# LiquidCrystal595.net
KiCad netlist of a schematic drawn in EAGLE
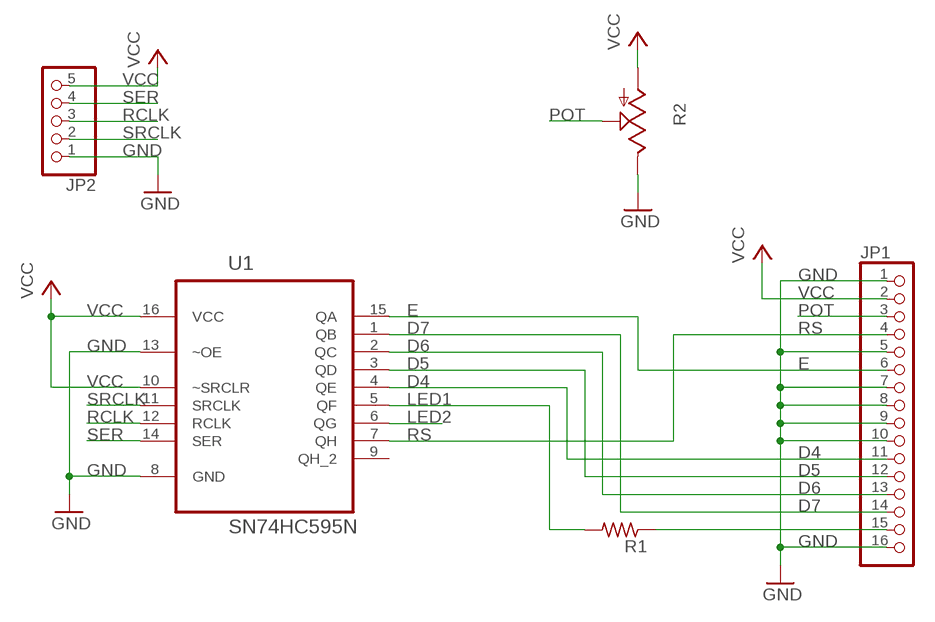
[diagram p0: schematic, sheet 1]

(export (version "E")
  (design (tool "Eeschema 10.0.6"))
  (components
    (comp (ref "JP1")
      (value "PINHD-1X16")
      (footprint "eagle-import:1X16")
      (libsource (lib "eagle-import") (part "PINHD-1X16"))
    )
    (comp (ref "JP2")
      (value "PINHD-1X5")
      (footprint "eagle-import:1X05")
      (libsource (lib "eagle-import") (part "PINHD-1X5"))
    )
    (comp (ref "R1")
      (value "R-US_0204/7")
      (footprint "eagle-import:0204_7")
      (libsource (lib "eagle-import") (part "R-US_0204/7"))
    )
    (comp (ref "R2")
      (value "TRIM_US-B25P")
      (footprint "eagle-import:B25P")
      (libsource (lib "eagle-import") (part "TRIM_US-B25P"))
    )
    (comp (ref "U1")
      (value "SN74HC595N")
      (footprint "eagle-import:DIP254P762X508-16")
      (libsource (lib "eagle-import") (part "SN74HC595N"))
    )
  )
  (nets
    (net (code "1") (name "/D4") (class "Default")
      (node (ref "JP1") (pin "11") (pinfunction "11_11") (pintype "passive"))
      (node (ref "U1") (pin "4") (pinfunction "QE_4") (pintype "output"))
    )
    (net (code "2") (name "/D5") (class "Default")
      (node (ref "JP1") (pin "12") (pinfunction "12_12") (pintype "passive"))
      (node (ref "U1") (pin "3") (pinfunction "QD_3") (pintype "output"))
    )
    (net (code "3") (name "/D6") (class "Default")
      (node (ref "JP1") (pin "13") (pinfunction "13_13") (pintype "passive"))
      (node (ref "U1") (pin "2") (pinfunction "QC_2") (pintype "output"))
    )
    (net (code "4") (name "/D7") (class "Default")
      (node (ref "JP1") (pin "14") (pinfunction "14_14") (pintype "passive"))
      (node (ref "U1") (pin "1") (pinfunction "QB_1") (pintype "output"))
    )
    (net (code "5") (name "/E") (class "Default")
      (node (ref "JP1") (pin "6") (pinfunction "6_6") (pintype "passive"))
      (node (ref "U1") (pin "15") (pinfunction "QA_15") (pintype "output"))
    )
    (net (code "6") (name "/LED1") (class "Default")
      (node (ref "R1") (pin "2") (pinfunction "2_2") (pintype "passive"))
      (node (ref "U1") (pin "5") (pinfunction "QF_5") (pintype "output"))
    )
    (net (code "7") (name "/LED2") (class "Default")
      (node (ref "U1") (pin "6") (pinfunction "QG_6") (pintype "output"))
    )
    (net (code "8") (name "/POT") (class "Default")
      (node (ref "JP1") (pin "3") (pinfunction "3_3") (pintype "passive"))
      (node (ref "R2") (pin "S") (pinfunction "S_S") (pintype "passive"))
    )
    (net (code "9") (name "/RCLK") (class "Default")
      (node (ref "JP2") (pin "3") (pinfunction "3_3") (pintype "passive"))
      (node (ref "U1") (pin "12") (pinfunction "RCLK_12") (pintype "input"))
    )
    (net (code "10") (name "/RS") (class "Default")
      (node (ref "JP1") (pin "4") (pinfunction "4_4") (pintype "passive"))
      (node (ref "U1") (pin "7") (pinfunction "QH_7") (pintype "output"))
    )
    (net (code "11") (name "/SER") (class "Default")
      (node (ref "JP2") (pin "4") (pinfunction "4_4") (pintype "passive"))
      (node (ref "U1") (pin "14") (pinfunction "SER_14") (pintype "input"))
    )
    (net (code "12") (name "/SRCLK") (class "Default")
      (node (ref "JP2") (pin "2") (pinfunction "2_2") (pintype "passive"))
      (node (ref "U1") (pin "11") (pinfunction "SRCLK_11") (pintype "input"))
    )
    (net (code "13") (name "GND") (class "Default")
      (node (ref "JP1") (pin "1") (pinfunction "1_1") (pintype "passive"))
      (node (ref "JP1") (pin "10") (pinfunction "10_10") (pintype "passive"))
      (node (ref "JP1") (pin "16") (pinfunction "16_16") (pintype "passive"))
      (node (ref "JP1") (pin "5") (pinfunction "5_5") (pintype "passive"))
      (node (ref "JP1") (pin "7") (pinfunction "7_7") (pintype "passive"))
      (node (ref "JP1") (pin "8") (pinfunction "8_8") (pintype "passive"))
      (node (ref "JP1") (pin "9") (pinfunction "9_9") (pintype "passive"))
      (node (ref "JP2") (pin "1") (pinfunction "1_1") (pintype "passive"))
      (node (ref "R2") (pin "E") (pinfunction "E_E") (pintype "passive"))
      (node (ref "U1") (pin "13") (pinfunction "~{OE}_13") (pintype "input"))
      (node (ref "U1") (pin "8") (pinfunction "GND_8") (pintype "passive"))
    )
    (net (code "14") (name "Net-(JP1-Pad15)") (class "Default")
      (node (ref "JP1") (pin "15") (pinfunction "15_15") (pintype "passive"))
      (node (ref "R1") (pin "1") (pinfunction "1_1") (pintype "passive"))
    )
    (net (code "15") (name "VCC") (class "Default")
      (node (ref "JP1") (pin "2") (pinfunction "2_2") (pintype "passive"))
      (node (ref "JP2") (pin "5") (pinfunction "5_5") (pintype "passive"))
      (node (ref "R2") (pin "A") (pinfunction "A_A") (pintype "passive"))
      (node (ref "U1") (pin "10") (pinfunction "~{SRCLR}_10") (pintype "input"))
      (node (ref "U1") (pin "16") (pinfunction "VCC_16") (pintype "power_in"))
    )
    (net (code "16") (name "unconnected-(U1-QH_2-Pad9)") (class "Default")
      (node (ref "U1") (pin "9") (pinfunction "QH_2_9") (pintype "output"))
    )
  )
)
